# MCU.net
KiCad netlist of a schematic drawn in Altium Designer
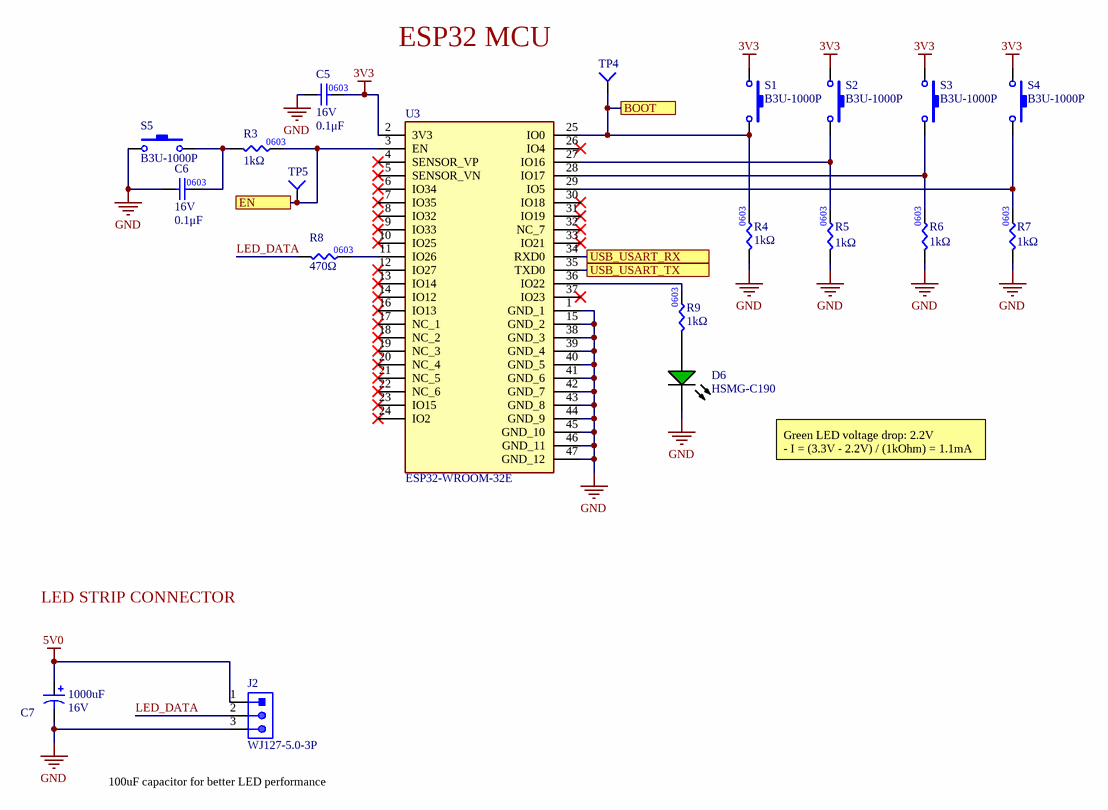
[diagram p0: MCU.SchDoc]

(export (version "E")
  (design (tool "Eeschema 10.0.6"))
  (components
    (comp (ref "C5")
      (value "0.1μF")
      (footprint "CAP0603")
      (description "CAP CER 0.1UF 16V X7R 0603")
      (fields (field (name "VOLTAGE RATING") "16V") (field (name "Comment") "CAP_0.1uF_16V_0603"))
      (libsource (lib "UWRT_Schematic_Library_2020") (part "CAP_0.1uF_16V_0603"))
    )
    (comp (ref "C6")
      (value "0.1μF")
      (footprint "CAP0603")
      (description "CAP CER 0.1UF 16V X7R 0603")
      (fields (field (name "VOLTAGE RATING") "16V") (field (name "Comment") "CAP_0.1uF_16V_0603"))
      (libsource (lib "UWRT_Schematic_Library_2020") (part "CAP_0.1uF_16V_0603"))
    )
    (comp (ref "C7")
      (value "CAP_1000uF_16V_ALUM")
      (footprint "CAPAE1030X1050N")
      (description "CAP ALUM 1000uF 20% 16V SMD")
      (fields
        (field (name "VOLTAGE") "16V")
        (field (name "MANUFACTURER") "Lelon")
        (field (name "TOLERANCE") "20%")
        (field (name "CAPACITANCE") "1000uF")
      )
      (libsource (lib "UWRT_Schematic_Library_2020") (part "CAP_1000uF_16V_ALUM"))
    )
    (comp (ref "D6")
      (value "HSMG-C190")
      (footprint "AVAG-HSMX-C190_V")
      (description "Chip LED, Green, 2.2 V, -40 to 85 degC, 2-Pin SMD, RoHS, Tape and Reel")
      (libsource (lib "Altium Content Vault") (part "LED-GREEN-AK-2"))
    )
    (comp (ref "J2")
      (value "WJ127-5.0-3P")
      (footprint "WJ127-5.0-3P")
      (libsource (lib "UWRT_Schematic_Library_2020") (part "WJ127-5.0-3P"))
    )
    (comp (ref "R3")
      (value "1kΩ")
      (footprint "RES0603")
      (description "RES 1K OHM 5% 1/10W 0603")
      (fields (field (name "Comment") "RES_1kΩ_0603_5%"))
      (libsource (lib "UWRT_Schematic_Library_2020") (part "RES_1kΩ_0603_5%"))
    )
    (comp (ref "R4")
      (value "1kΩ")
      (footprint "RES0603")
      (description "RES 1K OHM 5% 1/10W 0603")
      (fields (field (name "Comment") "RES_1kΩ_0603_5%"))
      (libsource (lib "UWRT_Schematic_Library_2020") (part "RES_1kΩ_0603_5%"))
    )
    (comp (ref "R5")
      (value "1kΩ")
      (footprint "RES0603")
      (description "RES 1K OHM 5% 1/10W 0603")
      (fields (field (name "Comment") "RES_1kΩ_0603_5%"))
      (libsource (lib "UWRT_Schematic_Library_2020") (part "RES_1kΩ_0603_5%"))
    )
    (comp (ref "R6")
      (value "1kΩ")
      (footprint "RES0603")
      (description "RES 1K OHM 5% 1/10W 0603")
      (fields (field (name "Comment") "RES_1kΩ_0603_5%"))
      (libsource (lib "UWRT_Schematic_Library_2020") (part "RES_1kΩ_0603_5%"))
    )
    (comp (ref "R7")
      (value "1kΩ")
      (footprint "RES0603")
      (description "RES 1K OHM 5% 1/10W 0603")
      (fields (field (name "Comment") "RES_1kΩ_0603_5%"))
      (libsource (lib "UWRT_Schematic_Library_2020") (part "RES_1kΩ_0603_5%"))
    )
    (comp (ref "R8")
      (value "470Ω")
      (footprint "RESC0603")
      (description "RES 470 OHM 1% 1/10W 0603")
      (fields (field (name "Comment") "470R 1%"))
      (libsource (lib "UWRT_Schematic_Library_2020") (part "RES_470Ω_0603_1%"))
    )
    (comp (ref "R9")
      (value "1kΩ")
      (footprint "RES0603")
      (description "RES 1K OHM 5% 1/10W 0603")
      (fields (field (name "Comment") "RES_1kΩ_0603_5%"))
      (libsource (lib "UWRT_Schematic_Library_2020") (part "RES_1kΩ_0603_5%"))
    )
    (comp (ref "S1")
      (value "SW_SPST_NO")
      (footprint "B3U-1000P")
      (description "SWITCH TACTILE SPST-NO 0.05A 12V")
      (fields (field (name "MANUFACTURER PART NUMBER 1") "B3U-1000P"))
      (libsource (lib "UWRT_Schematic_Library_2020") (part "SW_SPST_NO"))
    )
    (comp (ref "S2")
      (value "SW_SPST_NO")
      (footprint "B3U-1000P")
      (description "SWITCH TACTILE SPST-NO 0.05A 12V")
      (fields (field (name "MANUFACTURER PART NUMBER 1") "B3U-1000P"))
      (libsource (lib "UWRT_Schematic_Library_2020") (part "SW_SPST_NO"))
    )
    (comp (ref "S3")
      (value "SW_SPST_NO")
      (footprint "B3U-1000P")
      (description "SWITCH TACTILE SPST-NO 0.05A 12V")
      (fields (field (name "MANUFACTURER PART NUMBER 1") "B3U-1000P"))
      (libsource (lib "UWRT_Schematic_Library_2020") (part "SW_SPST_NO"))
    )
    (comp (ref "S4")
      (value "SW_SPST_NO")
      (footprint "B3U-1000P")
      (description "SWITCH TACTILE SPST-NO 0.05A 12V")
      (fields (field (name "MANUFACTURER PART NUMBER 1") "B3U-1000P"))
      (libsource (lib "UWRT_Schematic_Library_2020") (part "SW_SPST_NO"))
    )
    (comp (ref "S5")
      (value "SW_SPST_NO")
      (footprint "B3U-1000P")
      (description "SWITCH TACTILE SPST-NO 0.05A 12V")
      (fields (field (name "MANUFACTURER PART NUMBER 1") "B3U-1000P"))
      (libsource (lib "UWRT_Schematic_Library_2020") (part "SW_SPST_NO"))
    )
    (comp (ref "TP4")
      (value "TESTPOINT_1MM_SQUARE")
      (footprint "TESTPOINT_SQUARE_1MM")
      (description "TESTPOINT 1MM SQUARE")
      (libsource (lib "UWRT_Schematic_Library_2020") (part "TESTPOINT_1MM_SQUARE"))
    )
    (comp (ref "TP5")
      (value "TESTPOINT_1MM_SQUARE")
      (footprint "TESTPOINT_SQUARE_1MM")
      (description "TESTPOINT 1MM SQUARE")
      (libsource (lib "UWRT_Schematic_Library_2020") (part "TESTPOINT_1MM_SQUARE"))
    )
    (comp (ref "U3")
      (value "ESP32-WROOM-32E")
      (footprint "ESP32-WROOM-32E")
      (libsource (lib "UWRT_Schematic_Library_2020") (part "ESP32-WROOM-32E"))
    )
  )
  (nets
    (net (code "1") (name "/BOOT") (class "Default")
      (node (ref "R4") (pin "2") (pinfunction "2_2") (pintype "passive"))
      (node (ref "S1") (pin "2") (pinfunction "2_2") (pintype "passive"))
      (node (ref "TP4") (pin "1") (pinfunction "=value_1") (pintype "passive"))
      (node (ref "U3") (pin "25") (pinfunction "IO0_25") (pintype "passive"))
    )
    (net (code "2") (name "/EN") (class "Default")
      (node (ref "R3") (pin "2") (pinfunction "2_2") (pintype "passive"))
      (node (ref "TP5") (pin "1") (pinfunction "=value_1") (pintype "passive"))
      (node (ref "U3") (pin "3") (pinfunction "EN_3") (pintype "passive"))
    )
    (net (code "3") (name "/LED_DATA") (class "Default")
      (node (ref "J2") (pin "2") (pinfunction "2_2") (pintype "passive"))
      (node (ref "R8") (pin "1") (pinfunction "1_1") (pintype "passive"))
    )
    (net (code "4") (name "/USB_USART_RX") (class "Default")
      (node (ref "U3") (pin "34") (pinfunction "RXD0_34") (pintype "passive"))
    )
    (net (code "5") (name "/USB_USART_TX") (class "Default")
      (node (ref "U3") (pin "35") (pinfunction "TXD0_35") (pintype "passive"))
    )
    (net (code "6") (name "3V3") (class "Default")
      (node (ref "C5") (pin "2") (pinfunction "2_2") (pintype "passive"))
      (node (ref "S1") (pin "1") (pinfunction "1_1") (pintype "passive"))
      (node (ref "S2") (pin "1") (pinfunction "1_1") (pintype "passive"))
      (node (ref "S3") (pin "1") (pinfunction "1_1") (pintype "passive"))
      (node (ref "S4") (pin "1") (pinfunction "1_1") (pintype "passive"))
      (node (ref "U3") (pin "2") (pinfunction "3V3_2") (pintype "passive"))
    )
    (net (code "7") (name "5V0") (class "Default")
      (node (ref "C7") (pin "1") (pinfunction "1_1") (pintype "passive"))
      (node (ref "J2") (pin "1") (pinfunction "1_1") (pintype "passive"))
    )
    (net (code "8") (name "GND") (class "Default")
      (node (ref "C5") (pin "1") (pinfunction "1_1") (pintype "passive"))
      (node (ref "C6") (pin "1") (pinfunction "1_1") (pintype "passive"))
      (node (ref "C7") (pin "2") (pinfunction "2_2") (pintype "passive"))
      (node (ref "D6") (pin "2") (pinfunction "K_2") (pintype "passive"))
      (node (ref "J2") (pin "3") (pinfunction "3_3") (pintype "passive"))
      (node (ref "R4") (pin "1") (pinfunction "1_1") (pintype "passive"))
      (node (ref "R5") (pin "1") (pinfunction "1_1") (pintype "passive"))
      (node (ref "R6") (pin "1") (pinfunction "1_1") (pintype "passive"))
      (node (ref "R7") (pin "1") (pinfunction "1_1") (pintype "passive"))
      (node (ref "S5") (pin "1") (pinfunction "1_1") (pintype "passive"))
      (node (ref "U3") (pin "1") (pinfunction "GND_1_1") (pintype "passive"))
      (node (ref "U3") (pin "15") (pinfunction "GND_2_15") (pintype "passive"))
      (node (ref "U3") (pin "38") (pinfunction "GND_3_38") (pintype "passive"))
      (node (ref "U3") (pin "39") (pinfunction "GND_4_39") (pintype "passive"))
      (node (ref "U3") (pin "40") (pinfunction "GND_5_40") (pintype "passive"))
      (node (ref "U3") (pin "41") (pinfunction "GND_6_41") (pintype "passive"))
      (node (ref "U3") (pin "42") (pinfunction "GND_7_42") (pintype "passive"))
      (node (ref "U3") (pin "43") (pinfunction "GND_8_43") (pintype "passive"))
      (node (ref "U3") (pin "44") (pinfunction "GND_9_44") (pintype "passive"))
      (node (ref "U3") (pin "45") (pinfunction "GND_10_45") (pintype "passive"))
      (node (ref "U3") (pin "46") (pinfunction "GND_11_46") (pintype "passive"))
      (node (ref "U3") (pin "47") (pinfunction "GND_12_47") (pintype "passive"))
    )
    (net (code "9") (name "Net-(C6-Pad2)") (class "Default")
      (node (ref "C6") (pin "2") (pinfunction "2_2") (pintype "passive"))
      (node (ref "R3") (pin "1") (pinfunction "1_1") (pintype "passive"))
      (node (ref "S5") (pin "2") (pinfunction "2_2") (pintype "passive"))
    )
    (net (code "10") (name "Net-(D6-A)") (class "Default")
      (node (ref "D6") (pin "1") (pinfunction "A_1") (pintype "passive"))
      (node (ref "R9") (pin "1") (pinfunction "1_1") (pintype "passive"))
    )
    (net (code "11") (name "Net-(U3-IO5)") (class "Default")
      (node (ref "R7") (pin "2") (pinfunction "2_2") (pintype "passive"))
      (node (ref "S4") (pin "2") (pinfunction "2_2") (pintype "passive"))
      (node (ref "U3") (pin "29") (pinfunction "IO5_29") (pintype "passive"))
    )
    (net (code "12") (name "Net-(U3-IO16)") (class "Default")
      (node (ref "R5") (pin "2") (pinfunction "2_2") (pintype "passive"))
      (node (ref "S2") (pin "2") (pinfunction "2_2") (pintype "passive"))
      (node (ref "U3") (pin "27") (pinfunction "IO16_27") (pintype "passive"))
    )
    (net (code "13") (name "Net-(U3-IO17)") (class "Default")
      (node (ref "R6") (pin "2") (pinfunction "2_2") (pintype "passive"))
      (node (ref "S3") (pin "2") (pinfunction "2_2") (pintype "passive"))
      (node (ref "U3") (pin "28") (pinfunction "IO17_28") (pintype "passive"))
    )
    (net (code "14") (name "Net-(U3-IO22)") (class "Default")
      (node (ref "R9") (pin "2") (pinfunction "2_2") (pintype "passive"))
      (node (ref "U3") (pin "36") (pinfunction "IO22_36") (pintype "passive"))
    )
    (net (code "15") (name "Net-(U3-IO26)") (class "Default")
      (node (ref "R8") (pin "2") (pinfunction "2_2") (pintype "passive"))
      (node (ref "U3") (pin "11") (pinfunction "IO26_11") (pintype "passive"))
    )
    (net (code "16") (name "unconnected-(U3-IO2-Pad24)") (class "Default")
      (node (ref "U3") (pin "24") (pinfunction "IO2_24") (pintype "passive+no_connect"))
    )
    (net (code "17") (name "unconnected-(U3-IO4-Pad26)") (class "Default")
      (node (ref "U3") (pin "26") (pinfunction "IO4_26") (pintype "passive+no_connect"))
    )
    (net (code "18") (name "unconnected-(U3-IO12-Pad14)") (class "Default")
      (node (ref "U3") (pin "14") (pinfunction "IO12_14") (pintype "passive+no_connect"))
    )
    (net (code "19") (name "unconnected-(U3-IO13-Pad16)") (class "Default")
      (node (ref "U3") (pin "16") (pinfunction "IO13_16") (pintype "passive+no_connect"))
    )
    (net (code "20") (name "unconnected-(U3-IO14-Pad13)") (class "Default")
      (node (ref "U3") (pin "13") (pinfunction "IO14_13") (pintype "passive+no_connect"))
    )
    (net (code "21") (name "unconnected-(U3-IO15-Pad23)") (class "Default")
      (node (ref "U3") (pin "23") (pinfunction "IO15_23") (pintype "passive+no_connect"))
    )
    (net (code "22") (name "unconnected-(U3-IO18-Pad30)") (class "Default")
      (node (ref "U3") (pin "30") (pinfunction "IO18_30") (pintype "passive+no_connect"))
    )
    (net (code "23") (name "unconnected-(U3-IO19-Pad31)") (class "Default")
      (node (ref "U3") (pin "31") (pinfunction "IO19_31") (pintype "passive+no_connect"))
    )
    (net (code "24") (name "unconnected-(U3-IO21-Pad33)") (class "Default")
      (node (ref "U3") (pin "33") (pinfunction "IO21_33") (pintype "passive+no_connect"))
    )
    (net (code "25") (name "unconnected-(U3-IO23-Pad37)") (class "Default")
      (node (ref "U3") (pin "37") (pinfunction "IO23_37") (pintype "passive+no_connect"))
    )
    (net (code "26") (name "unconnected-(U3-IO25-Pad10)") (class "Default")
      (node (ref "U3") (pin "10") (pinfunction "IO25_10") (pintype "passive+no_connect"))
    )
    (net (code "27") (name "unconnected-(U3-IO27-Pad12)") (class "Default")
      (node (ref "U3") (pin "12") (pinfunction "IO27_12") (pintype "passive+no_connect"))
    )
    (net (code "28") (name "unconnected-(U3-IO32-Pad8)") (class "Default")
      (node (ref "U3") (pin "8") (pinfunction "IO32_8") (pintype "passive+no_connect"))
    )
    (net (code "29") (name "unconnected-(U3-IO33-Pad9)") (class "Default")
      (node (ref "U3") (pin "9") (pinfunction "IO33_9") (pintype "passive+no_connect"))
    )
    (net (code "30") (name "unconnected-(U3-IO34-Pad6)") (class "Default")
      (node (ref "U3") (pin "6") (pinfunction "IO34_6") (pintype "passive+no_connect"))
    )
    (net (code "31") (name "unconnected-(U3-IO35-Pad7)") (class "Default")
      (node (ref "U3") (pin "7") (pinfunction "IO35_7") (pintype "passive+no_connect"))
    )
    (net (code "32") (name "unconnected-(U3-NC_1-Pad17)") (class "Default")
      (node (ref "U3") (pin "17") (pinfunction "NC_1_17") (pintype "passive+no_connect"))
    )
    (net (code "33") (name "unconnected-(U3-NC_2-Pad18)") (class "Default")
      (node (ref "U3") (pin "18") (pinfunction "NC_2_18") (pintype "passive+no_connect"))
    )
    (net (code "34") (name "unconnected-(U3-NC_3-Pad19)") (class "Default")
      (node (ref "U3") (pin "19") (pinfunction "NC_3_19") (pintype "passive+no_connect"))
    )
    (net (code "35") (name "unconnected-(U3-NC_4-Pad20)") (class "Default")
      (node (ref "U3") (pin "20") (pinfunction "NC_4_20") (pintype "passive+no_connect"))
    )
    (net (code "36") (name "unconnected-(U3-NC_5-Pad21)") (class "Default")
      (node (ref "U3") (pin "21") (pinfunction "NC_5_21") (pintype "passive+no_connect"))
    )
    (net (code "37") (name "unconnected-(U3-NC_6-Pad22)") (class "Default")
      (node (ref "U3") (pin "22") (pinfunction "NC_6_22") (pintype "passive+no_connect"))
    )
    (net (code "38") (name "unconnected-(U3-NC_7-Pad32)") (class "Default")
      (node (ref "U3") (pin "32") (pinfunction "NC_7_32") (pintype "passive+no_connect"))
    )
    (net (code "39") (name "unconnected-(U3-SENSOR_VN-Pad5)") (class "Default")
      (node (ref "U3") (pin "5") (pinfunction "SENSOR_VN_5") (pintype "passive+no_connect"))
    )
    (net (code "40") (name "unconnected-(U3-SENSOR_VP-Pad4)") (class "Default")
      (node (ref "U3") (pin "4") (pinfunction "SENSOR_VP_4") (pintype "passive+no_connect"))
    )
  )
)
